# metal_detector.net
KiCad netlist of a schematic drawn in EAGLE
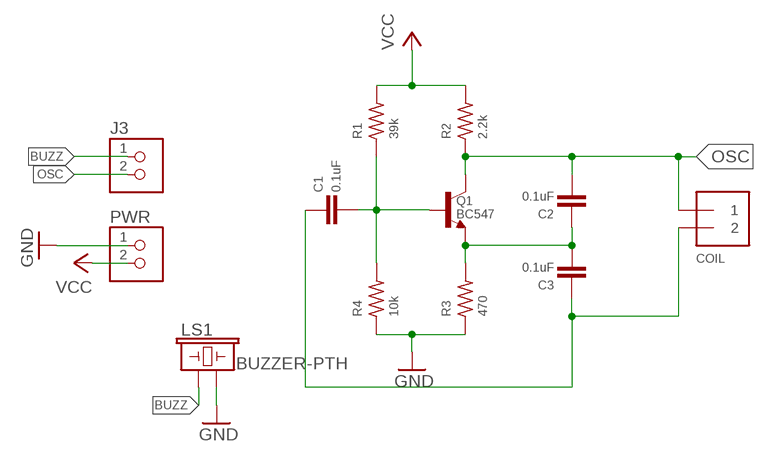
[diagram p0: schematic, sheet 1]

(export (version "E")
  (design (tool "Eeschema 10.0.6"))
  (components
    (comp (ref "C1")
      (value "0.1uF")
      (footprint "eagle-import:CAP-PTH-SMALL-KIT")
      (libsource (lib "eagle-import") (part "0.1UF-KIT-EZ-50V-20%"))
    )
    (comp (ref "C2")
      (value "0.1uF")
      (footprint "eagle-import:CAP-PTH-SMALL-KIT")
      (libsource (lib "eagle-import") (part "0.1UF-KIT-EZ-50V-20%"))
    )
    (comp (ref "C3")
      (value "0.1uF")
      (footprint "eagle-import:CAP-PTH-SMALL-KIT")
      (libsource (lib "eagle-import") (part "0.1UF-KIT-EZ-50V-20%"))
    )
    (comp (ref "COIL")
      (value "TERMBLOCK_1X2")
      (footprint "eagle-import:TERMBLOCK_1X2-3.5MM")
      (libsource (lib "eagle-import") (part "TERMBLOCK_1X2"))
    )
    (comp (ref "J3")
      (value "TERM-1X02-ADAFRUIT")
      (footprint "eagle-import:3.5MMTERM")
      (libsource (lib "eagle-import") (part "TERM-1X02-ADAFRUIT"))
    )
    (comp (ref "LS1")
      (value "BUZZER-PTH")
      (footprint "eagle-import:BUZZER-12MM")
      (libsource (lib "eagle-import") (part "BUZZER-PTH"))
    )
    (comp (ref "PWR")
      (value "TERM-1X02-ADAFRUIT")
      (footprint "eagle-import:3.5MMTERM")
      (libsource (lib "eagle-import") (part "TERM-1X02-ADAFRUIT"))
    )
    (comp (ref "Q1")
      (value "BC547")
      (footprint "eagle-import:TO92")
      (libsource (lib "eagle-import") (part "BC547"))
    )
    (comp (ref "R1")
      (value "39k")
      (footprint "eagle-import:0207_10")
      (libsource (lib "eagle-import") (part "R-US_0207/10"))
    )
    (comp (ref "R2")
      (value "2.2k")
      (footprint "eagle-import:0207_10")
      (libsource (lib "eagle-import") (part "R-US_0207/10"))
    )
    (comp (ref "R3")
      (value "470")
      (footprint "eagle-import:0207_10")
      (libsource (lib "eagle-import") (part "R-US_0207/10"))
    )
    (comp (ref "R4")
      (value "10k")
      (footprint "eagle-import:0207_10")
      (libsource (lib "eagle-import") (part "R-US_0207/10"))
    )
  )
  (nets
    (net (code "1") (name "BUZZ") (class "Default")
      (node (ref "J3") (pin "1") (pinfunction "1_1") (pintype "passive"))
      (node (ref "LS1") (pin "+") (pinfunction "1_+") (pintype "passive"))
    )
    (net (code "2") (name "GND") (class "Default")
      (node (ref "LS1") (pin "-") (pinfunction "2_-") (pintype "passive"))
      (node (ref "PWR") (pin "1") (pinfunction "1_1") (pintype "passive"))
      (node (ref "R3") (pin "1") (pinfunction "1_1") (pintype "passive"))
      (node (ref "R4") (pin "1") (pinfunction "1_1") (pintype "passive"))
    )
    (net (code "3") (name "Net-(C1-Pad1)") (class "Default")
      (node (ref "C1") (pin "1") (pinfunction "1_1") (pintype "passive"))
      (node (ref "C3") (pin "1") (pinfunction "1_1") (pintype "passive"))
      (node (ref "COIL") (pin "2") (pinfunction "2_2") (pintype "passive"))
    )
    (net (code "4") (name "Net-(Q1-B)") (class "Default")
      (node (ref "C1") (pin "2") (pinfunction "2_2") (pintype "passive"))
      (node (ref "Q1") (pin "2") (pinfunction "B_2") (pintype "passive"))
      (node (ref "R1") (pin "1") (pinfunction "1_1") (pintype "passive"))
      (node (ref "R4") (pin "2") (pinfunction "2_2") (pintype "passive"))
    )
    (net (code "5") (name "Net-(Q1-E)") (class "Default")
      (node (ref "C2") (pin "1") (pinfunction "1_1") (pintype "passive"))
      (node (ref "C3") (pin "2") (pinfunction "2_2") (pintype "passive"))
      (node (ref "Q1") (pin "1") (pinfunction "E_1") (pintype "passive"))
      (node (ref "R3") (pin "2") (pinfunction "2_2") (pintype "passive"))
    )
    (net (code "6") (name "OSC") (class "Default")
      (node (ref "C2") (pin "2") (pinfunction "2_2") (pintype "passive"))
      (node (ref "COIL") (pin "1") (pinfunction "1_1") (pintype "passive"))
      (node (ref "J3") (pin "2") (pinfunction "2_2") (pintype "passive"))
      (node (ref "Q1") (pin "3") (pinfunction "C_3") (pintype "passive"))
      (node (ref "R2") (pin "1") (pinfunction "1_1") (pintype "passive"))
    )
    (net (code "7") (name "VCC") (class "Default")
      (node (ref "PWR") (pin "2") (pinfunction "2_2") (pintype "passive"))
      (node (ref "R1") (pin "2") (pinfunction "2_2") (pintype "passive"))
      (node (ref "R2") (pin "2") (pinfunction "2_2") (pintype "passive"))
    )
  )
)
